# attiny-batt-board-15mm-mk-1.net
KiCad netlist of a schematic drawn in EAGLE
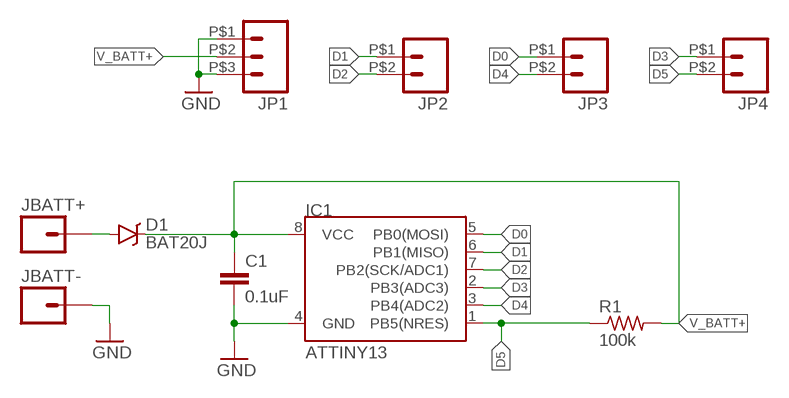
[diagram p0: schematic, sheet 1]

(export (version "E")
  (design (tool "Eeschema 10.0.6"))
  (components
    (comp (ref "C1")
      (value "0.1uF")
      (footprint "eagle-import:C0603")
      (libsource (lib "eagle-import") (part "CAPACITOR-CERAMICC0603"))
    )
    (comp (ref "D1")
      (value "BAT20J")
      (footprint "eagle-import:SOD-323")
      (libsource (lib "eagle-import") (part "DIODE-SCHOTTKYBAT20J"))
    )
    (comp (ref "IC1")
      (value "ATTINY13")
      (footprint "eagle-import:SO08")
      (libsource (lib "eagle-import") (part "ATTINY13SOIC"))
    )
    (comp (ref "JBATT+")
      (value "M01NOT-A-VIA-NOPE")
      (footprint "eagle-import:1X01_NOSILK_NOSTOP")
      (libsource (lib "eagle-import") (part "M01NOT-A-VIA-NOPE"))
    )
    (comp (ref "JBATT-")
      (value "M01NOT-A-VIA-NOPE")
      (footprint "eagle-import:1X01_NOSILK_NOSTOP")
      (libsource (lib "eagle-import") (part "M01NOT-A-VIA-NOPE"))
    )
    (comp (ref "JP1")
      (value "M03PTH-2MM")
      (footprint "eagle-import:1X03-2MM-PTH")
      (libsource (lib "eagle-import") (part "M03PTH-2MM"))
    )
    (comp (ref "JP2")
      (value "M02PTH-2MM")
      (footprint "eagle-import:1X02-2MM-PTH")
      (libsource (lib "eagle-import") (part "M02PTH-2MM"))
    )
    (comp (ref "JP3")
      (value "M02PTH-2MM")
      (footprint "eagle-import:1X02-2MM-PTH")
      (libsource (lib "eagle-import") (part "M02PTH-2MM"))
    )
    (comp (ref "JP4")
      (value "M02PTH-2MM")
      (footprint "eagle-import:1X02-2MM-PTH")
      (libsource (lib "eagle-import") (part "M02PTH-2MM"))
    )
    (comp (ref "R1")
      (value "100k")
      (footprint "eagle-import:R0603")
      (libsource (lib "eagle-import") (part "RESISTORR0603"))
    )
  )
  (nets
    (net (code "1") (name "D0") (class "Default")
      (node (ref "IC1") (pin "5") (pinfunction "PB0(MOSI)_5") (pintype "bidirectional"))
      (node (ref "JP3") (pin "P$1") (pinfunction "1_P$1") (pintype "passive"))
    )
    (net (code "2") (name "D1") (class "Default")
      (node (ref "IC1") (pin "6") (pinfunction "PB1(MISO)_6") (pintype "bidirectional"))
      (node (ref "JP2") (pin "P$1") (pinfunction "1_P$1") (pintype "passive"))
    )
    (net (code "3") (name "D2") (class "Default")
      (node (ref "IC1") (pin "7") (pinfunction "PB2(SCK/ADC1)_7") (pintype "bidirectional"))
      (node (ref "JP2") (pin "P$2") (pinfunction "2_P$2") (pintype "passive"))
    )
    (net (code "4") (name "D3") (class "Default")
      (node (ref "IC1") (pin "2") (pinfunction "PB3(ADC3)_2") (pintype "bidirectional"))
      (node (ref "JP4") (pin "P$1") (pinfunction "1_P$1") (pintype "passive"))
    )
    (net (code "5") (name "D4") (class "Default")
      (node (ref "IC1") (pin "3") (pinfunction "PB4(ADC2)_3") (pintype "bidirectional"))
      (node (ref "JP3") (pin "P$2") (pinfunction "2_P$2") (pintype "passive"))
    )
    (net (code "6") (name "D5") (class "Default")
      (node (ref "IC1") (pin "1") (pinfunction "PB5(NRES)_1") (pintype "bidirectional"))
      (node (ref "JP4") (pin "P$2") (pinfunction "2_P$2") (pintype "passive"))
      (node (ref "R1") (pin "1") (pinfunction "1_1") (pintype "passive"))
    )
    (net (code "7") (name "GND") (class "Default")
      (node (ref "C1") (pin "2") (pinfunction "2_2") (pintype "passive"))
      (node (ref "IC1") (pin "4") (pinfunction "GND_4") (pintype "bidirectional"))
      (node (ref "JBATT-") (pin "P$1") (pinfunction "1_P$1") (pintype "passive"))
      (node (ref "JP1") (pin "P$1") (pinfunction "1_P$1") (pintype "passive"))
      (node (ref "JP1") (pin "P$3") (pinfunction "3_P$3") (pintype "passive"))
    )
    (net (code "8") (name "Net-(JBATT+-1)") (class "Default")
      (node (ref "D1") (pin "A") (pinfunction "A_A") (pintype "passive"))
      (node (ref "JBATT+") (pin "P$1") (pinfunction "1_P$1") (pintype "passive"))
    )
    (net (code "9") (name "V_BATT+") (class "Default")
      (node (ref "C1") (pin "1") (pinfunction "1_1") (pintype "passive"))
      (node (ref "D1") (pin "C") (pinfunction "C_C") (pintype "passive"))
      (node (ref "IC1") (pin "8") (pinfunction "VCC_8") (pintype "bidirectional"))
      (node (ref "JP1") (pin "P$2") (pinfunction "2_P$2") (pintype "passive"))
      (node (ref "R1") (pin "2") (pinfunction "2_2") (pintype "passive"))
    )
  )
)
